# CameraCageBB.net
KiCad netlist of a schematic drawn in Altium Designer
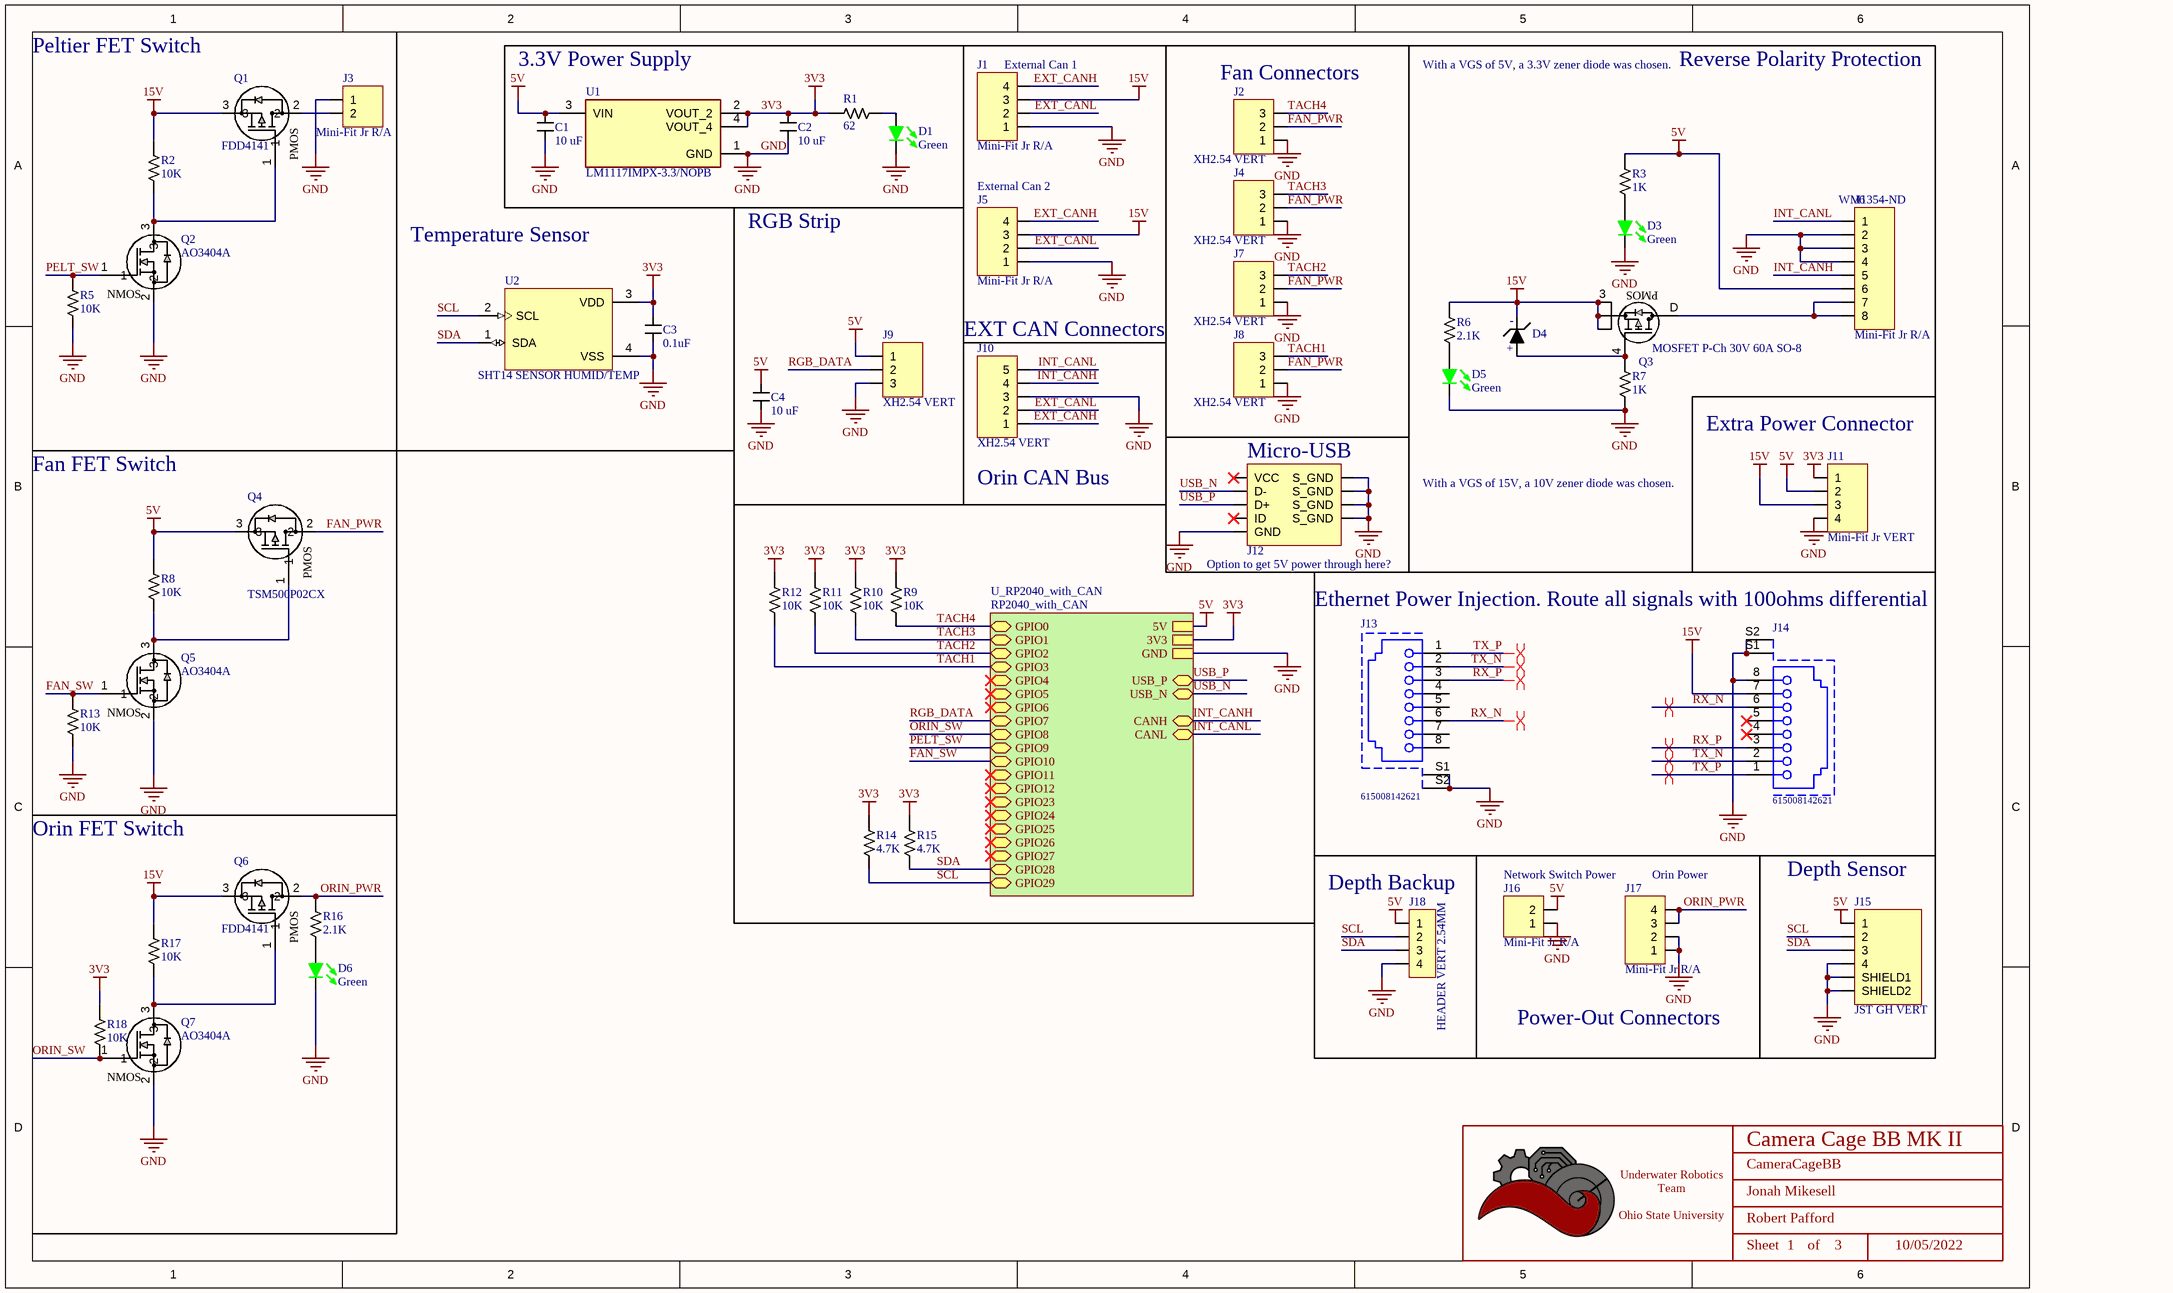
[diagram p0: CameraCageBB.SchDoc]

(export (version "E")
  (design (tool "Eeschema 10.0.6"))
  (components
    (comp (ref "*")
      (value "Title_Block")
      (footprint "LOGO")
      (description "UWRT Schematic Title Block Template\r\n\r\nCreated June 2021, Dylan Trainor")
      (libsource (lib "UWRT") (part "Title_Block"))
    )
    (comp (ref "C1")
      (value "10uF Ceramic 6.3V")
      (footprint "CAPACITOR_0603")
      (description "Cap 10uF 6.3V +/-20%\r\nCeramic 0603")
      (fields
        (field (name "TOLERANCE") "+/- 20%")
        (field (name "VOLTAGE") "6.3V")
        (field (name "VALUE (UF)") "10 uF")
        (field (name "MADE BY") "Flip B")
      )
      (libsource (lib "Capacitors") (part "CAPACITOR_10uF_0603"))
    )
    (comp (ref "C2")
      (value "10uF Ceramic 6.3V")
      (footprint "CAPACITOR_0603")
      (description "Cap 10uF 6.3V +/-20%\r\nCeramic 0603")
      (fields
        (field (name "TOLERANCE") "+/- 20%")
        (field (name "VOLTAGE") "6.3V")
        (field (name "VALUE (UF)") "10 uF")
        (field (name "MADE BY") "Flip B")
      )
      (libsource (lib "Capacitors") (part "CAPACITOR_10uF_0603"))
    )
    (comp (ref "C3")
      (value "0.1uF")
      (footprint "CAPACITOR_0603")
      (description "Cap 100nF 6.3V +/-10%\r\nCeramic 0603")
      (fields
        (field (name "TOLERANCE") "+/- 10%")
        (field (name "VOLTAGE") "6.3V")
        (field (name "MADE BY") "Flip B")
      )
      (libsource (lib "Capacitors") (part "CAPACITOR_0.1uF_0603"))
    )
    (comp (ref "C4")
      (value "10uF Ceramic 6.3V")
      (footprint "CAPACITOR_0603")
      (description "Cap 10uF 6.3V +/-20%\r\nCeramic 0603")
      (fields
        (field (name "TOLERANCE") "+/- 20%")
        (field (name "VOLTAGE") "6.3V")
        (field (name "VALUE (UF)") "10 uF")
        (field (name "MADE BY") "Flip B")
      )
      (libsource (lib "Capacitors") (part "CAPACITOR_10uF_0603"))
    )
    (comp (ref "D1")
      (value "IN-S63AT5G")
      (footprint "LED_0603")
      (description "LED Green Vf= 3V If = 0.005A\r\nIN-S63AT5G")
      (fields (field (name "COLOR") "Green") (field (name "MADE BY") "Robert Pafford"))
      (libsource (lib "Diodes") (part "LED_Green_0603_3V"))
    )
    (comp (ref "D3")
      (value "IN-S63AT5G")
      (footprint "LED_0603")
      (description "LED Green Vf= 3V If = 0.005A\r\nIN-S63AT5G")
      (fields (field (name "COLOR") "Green") (field (name "MADE BY") "Robert Pafford"))
      (libsource (lib "Diodes") (part "LED_Green_0603_3V"))
    )
    (comp (ref "D4")
      (value "Zener_Diode_10V_410mW")
      (footprint "SOD-123")
      (description "Zener Diode ¦ 10 V ¦ 410 mW ¦ SOD 123")
      (fields (field (name "POWER") "410mW") (field (name "MADE BY") "Nathan A"))
      (libsource (lib "Diodes") (part "Zener_Diode_10V_410mW"))
    )
    (comp (ref "D5")
      (value "IN-S63AT5G")
      (footprint "LED_0603")
      (description "LED Green Vf= 3V If = 0.005A\r\nIN-S63AT5G")
      (fields (field (name "COLOR") "Green") (field (name "MADE BY") "Robert Pafford"))
      (libsource (lib "Diodes") (part "LED_Green_0603_3V"))
    )
    (comp (ref "D6")
      (value "IN-S63AT5G")
      (footprint "LED_0603")
      (description "LED Green Vf= 3V If = 0.005A\r\nIN-S63AT5G")
      (fields (field (name "COLOR") "Green") (field (name "MADE BY") "Robert Pafford"))
      (libsource (lib "Diodes") (part "LED_Green_0603_3V"))
    )
    (comp (ref "J1")
      (value "Mini-Fit Jr R/A")
      (footprint "CONN_MOLEX_MINIFIT JR_4 POS_R/A")
      (description "Molex Minifit Jr. 5569 \r\n4 Pos R/A Natural")
      (fields (field (name "MANUFACTURER") "Molex") (field (name "CREATED BY") "Flip B"))
      (libsource (lib "Connectors") (part "CONN_MOLEX_MINIFIT JR_4POS_R/A"))
    )
    (comp (ref "J2")
      (value "XH2.54 VERT")
      (footprint "CONN_JST_XH254_3POS_VERT")
      (description "JST XH 2.54mm Pitch 3 Pos Vertical")
      (fields (field (name "MANUFACTURER") "JST") (field (name "CREATED BY") "Robert P"))
      (libsource (lib "") (part "CONN_JST_XH254_3POS_VERT_1"))
    )
    (comp (ref "J3")
      (value "Mini-Fit Jr R/A")
      (footprint "CONN_MOLEX_MINIFIT JR_2 POS_R/A")
      (description "Molex Minifit Jr. 5569 \r\n2 Pos R/A Natural")
      (fields (field (name "MANUFACTURER") "Molex") (field (name "CREATED BY") "Robert P"))
      (libsource (lib "Connectors") (part "CONN_MOLEX_MINIFIT JR_2POS_R/A"))
    )
    (comp (ref "J4")
      (value "XH2.54 VERT")
      (footprint "CONN_JST_XH254_3POS_VERT")
      (description "JST XH 2.54mm Pitch 3 Pos Vertical")
      (fields (field (name "MANUFACTURER") "JST") (field (name "CREATED BY") "Robert P"))
      (libsource (lib "") (part "CONN_JST_XH254_3POS_VERT_1"))
    )
    (comp (ref "J5")
      (value "Mini-Fit Jr R/A")
      (footprint "CONN_MOLEX_MINIFIT JR_4 POS_R/A")
      (description "Molex Minifit Jr. 5569 \r\n4 Pos R/A Natural")
      (fields (field (name "MANUFACTURER") "Molex") (field (name "CREATED BY") "Flip B"))
      (libsource (lib "Connectors") (part "CONN_MOLEX_MINIFIT JR_4POS_R/A"))
    )
    (comp (ref "J6")
      (value "Mini-Fit Jr R/A")
      (footprint "CONN_MOLEX_MINIFIT JR_8 POS_R/A")
      (description "Molex Minifit Jr. 5569 \r\n8 Pos R/A Natural")
      (fields
        (field (name "MANUFACTURER") "Molex")
        (field (name "SUPPLIER PART NUMBER 1") "WM1354-ND")
        (field (name "CREATED BY") "Flip B")
      )
      (libsource (lib "Connectors") (part "CONN_MOLEX_MINIFIT JR_8POS_R/A"))
    )
    (comp (ref "J7")
      (value "XH2.54 VERT")
      (footprint "CONN_JST_XH254_3POS_VERT")
      (description "JST XH 2.54mm Pitch 3 Pos Vertical")
      (fields (field (name "MANUFACTURER") "JST") (field (name "CREATED BY") "Robert P"))
      (libsource (lib "") (part "CONN_JST_XH254_3POS_VERT_1"))
    )
    (comp (ref "J8")
      (value "XH2.54 VERT")
      (footprint "CONN_JST_XH254_3POS_VERT")
      (description "JST XH 2.54mm Pitch 3 Pos Vertical")
      (fields (field (name "MANUFACTURER") "JST") (field (name "CREATED BY") "Robert P"))
      (libsource (lib "") (part "CONN_JST_XH254_3POS_VERT_1"))
    )
    (comp (ref "J9")
      (value "XH2.54 VERT")
      (footprint "CONN_JST_XH254_3POS_VERT")
      (description "JST XH 2.54mm Pitch 3 Pos Vertical")
      (fields (field (name "MANUFACTURER") "JST") (field (name "CREATED BY") "Robert P"))
      (libsource (lib "Connectors") (part "CONN_JST_XH254_3POS_VERT"))
    )
    (comp (ref "J10")
      (value "XH2.54 VERT")
      (footprint "CONN_JST_XH254_5POS_VERT")
      (description "JST XH 2.54mm Pitch 5 Pos Vertical")
      (fields (field (name "MANUFACTURER") "JST") (field (name "CREATED BY") "Robert P"))
      (libsource (lib "Connectors") (part "CONN_JST_XH254_5POS_VERT"))
    )
    (comp (ref "J11")
      (value "Mini-Fit Jr VERT")
      (footprint "CONN_MOLEX_MINIFIT JR_4 POS_VERT")
      (description "Molex Minifit Jr. 5566 \r\n4 Pos Vertical Natural")
      (fields (field (name "MANUFACTURER") "Molex") (field (name "CREATED BY") "Robert P"))
      (libsource (lib "Connectors") (part "CONN_MOLEX_MINIFIT JR_4POS_VERT"))
    )
    (comp (ref "J12")
      (value "USB_MICRO R/A")
      (footprint "CONN_MINIUSB")
      (description "Amphenol Micro USB-B\r\nUSB2.0 5 Pin Right Angle SMD")
      (fields (field (name "MANUFACTURER") "Amphenol") (field (name "CREATED BY") "Flip B"))
      (libsource (lib "Connectors") (part "CONN_MICROUSB"))
    )
    (comp (ref "J13")
      (value "615008142621")
      (footprint "615008142621")
      (fields (field (name "MANUFACTURER") "Wurth Elektronik") (field (name "PUBLISHER") "WurthElektronik"))
      (libsource (lib "Altium Content Vault") (part "WE-CN-1P-2F-J8"))
    )
    (comp (ref "J14")
      (value "615008142621")
      (footprint "615008142621")
      (fields (field (name "MANUFACTURER") "Wurth Elektronik") (field (name "PUBLISHER") "WurthElektronik"))
      (libsource (lib "Altium Content Vault") (part "WE-CN-1P-2F-J8"))
    )
    (comp (ref "J15")
      (value "JST GH VERT")
      (footprint "CONN_JST_BM04B-GHS-TBT(LF)(SN)(N)")
      (description "JST GH Pitch 4 Pos Vertical")
      (fields (field (name "MANUFACTURER") "JST") (field (name "CREATED BY") "Robert P"))
      (libsource (lib "Connectors") (part "CONN_JST_GH_4POS_VERT"))
    )
    (comp (ref "J16")
      (value "Mini-Fit Jr R/A")
      (footprint "CONN_MOLEX_MINIFIT JR_2 POS_R/A")
      (description "Molex Minifit Jr. 5569 \r\n2 Pos R/A Natural")
      (fields (field (name "MANUFACTURER") "Molex") (field (name "CREATED BY") "Robert P"))
      (libsource (lib "") (part "CONN_MOLEX_MINIFIT JR_2POS_R/A_1"))
    )
    (comp (ref "J17")
      (value "Mini-Fit Jr R/A")
      (footprint "CONN_MOLEX_MINIFIT JR_4 POS_R/A")
      (description "Molex Minifit Jr. 5569 \r\n4 Pos R/A Natural")
      (fields (field (name "MANUFACTURER") "Molex") (field (name "CREATED BY") "Flip B"))
      (libsource (lib "Connectors") (part "CONN_MOLEX_MINIFIT JR_4POS_R/A"))
    )
    (comp (ref "J18")
      (value "HEADER VERT 2.54MM")
      (footprint "HEADER_4PIN_2.54MM")
      (description "CONN HEADER VERT 4POS 2.54MM")
      (fields (field (name "MADE BY") "Robert Pafford"))
      (libsource (lib "Connectors") (part "HEADER_4PIN_2.54MM"))
    )
    (comp (ref "Q1")
      (value "FDD4141")
      (footprint "DPAK_ONS")
      (description "P-Channel 10.8A (Ta), 50A (Tc) 2.4W (Ta), 69W (Tc) Surface Mount D-PAK (TO-252AA)")
      (fields (field (name "CREATED BY") "Dylan T"))
      (libsource (lib "Transistors") (part "FDD4141"))
    )
    (comp (ref "Q2")
      (value "AO3404A")
      (footprint "SOT-23-3")
      (description "N-Channel 30 V 5.8A (Ta) 1.4W (Ta) Surface Mount SOT-23-3")
      (fields (field (name "CREATED BY") "Dylan T"))
      (libsource (lib "Transistors") (part "AO3404A"))
    )
    (comp (ref "Q3")
      (value "MOSFET P-Ch 30V 60A SO-8")
      (footprint "MOSFET_7DP-T1-GE3_VIS")
      (description "P-Channel 30 V 60A (Tc) 65.8W (Tc) Surface Mount PowerPAK® SO-8")
      (fields
        (field (name "MANUFACTURER_PART_NUMBER") "SIR167DP-T1-GE3")
        (field (name "COPYRIGHT") "Copyright (C) 2022 Ultra Librarian. All rights reserved.")
      )
      (libsource (lib "Transistors") (part "SIR167DP-T1-GE3"))
    )
    (comp (ref "Q4")
      (value "TSM500P02CX")
      (footprint "SOT-23-3")
      (description "P-Channel 20 V 4.7A (Tc) 1.56W (Tc) Surface Mount SOT-23")
      (fields (field (name "CREATED BY") "Robert Pafford"))
      (libsource (lib "Transistors") (part "TSM500P02CX"))
    )
    (comp (ref "Q5")
      (value "AO3404A")
      (footprint "SOT-23-3")
      (description "N-Channel 30 V 5.8A (Ta) 1.4W (Ta) Surface Mount SOT-23-3")
      (fields (field (name "CREATED BY") "Dylan T"))
      (libsource (lib "Transistors") (part "AO3404A"))
    )
    (comp (ref "Q6")
      (value "FDD4141")
      (footprint "DPAK_ONS")
      (description "P-Channel 10.8A (Ta), 50A (Tc) 2.4W (Ta), 69W (Tc) Surface Mount D-PAK (TO-252AA)")
      (fields (field (name "CREATED BY") "Dylan T"))
      (libsource (lib "Transistors") (part "FDD4141"))
    )
    (comp (ref "Q7")
      (value "AO3404A")
      (footprint "SOT-23-3")
      (description "N-Channel 30 V 5.8A (Ta) 1.4W (Ta) Surface Mount SOT-23-3")
      (fields (field (name "CREATED BY") "Dylan T"))
      (libsource (lib "Transistors") (part "AO3404A"))
    )
    (comp (ref "R1")
      (value "62 Ohm 1% 1/4W")
      (footprint "RESISTOR_0603")
      (description "RES SMD 62 OHM 1% 1/4W 0603")
      (fields
        (field (name "TOLERANCE") "+/- 1%")
        (field (name "VALUE  (OHMS)") "62")
        (field (name "MADE BY") "Robert Pafford")
      )
      (libsource (lib "Resistors") (part "RESISTOR_62_0603"))
    )
    (comp (ref "R2")
      (value "10k Ohm 5% 1/10W")
      (footprint "RESISTOR_0603")
      (description "RES 10k OHM 5% 1/10W 0603")
      (fields
        (field (name "TOLERANCE") "+/- 5%")
        (field (name "VALUE  (OHMS)") "10K")
        (field (name "MADE BY") "Robert Pafford")
      )
      (libsource (lib "Resistors") (part "RESISTOR_10K_0603"))
    )
    (comp (ref "R3")
      (value "1k Ohm 5% 1/8W")
      (footprint "RESISTOR_0603")
      (description "RES 1k OHM 5% 1/8W 0603")
      (fields
        (field (name "TOLERANCE") "+/- 5%")
        (field (name "VALUE  (OHMS)") "1K")
        (field (name "MADE BY") "Robert Pafford")
      )
      (libsource (lib "Resistors") (part "RESISTOR_1K_0603"))
    )
    (comp (ref "R5")
      (value "10k Ohm 5% 1/10W")
      (footprint "RESISTOR_0603")
      (description "RES 10k OHM 5% 1/10W 0603")
      (fields
        (field (name "TOLERANCE") "+/- 5%")
        (field (name "VALUE  (OHMS)") "10K")
        (field (name "MADE BY") "Robert Pafford")
      )
      (libsource (lib "Resistors") (part "RESISTOR_10K_0603"))
    )
    (comp (ref "R6")
      (value "2.1k Ohm 5% 1/8W")
      (footprint "RESISTOR_0603")
      (description "RES 2.1k OHM 5% 1/8W 0603")
      (fields
        (field (name "TOLERANCE") "+/- 5%")
        (field (name "VALUE  (OHMS)") "2.1K")
        (field (name "MADE BY") "Robert Pafford")
      )
      (libsource (lib "Resistors") (part "RESISTOR_2.1K_0603"))
    )
    (comp (ref "R7")
      (value "1k Ohm 5% 1/8W")
      (footprint "RESISTOR_0603")
      (description "RES 1k OHM 5% 1/8W 0603")
      (fields
        (field (name "TOLERANCE") "+/- 5%")
        (field (name "VALUE  (OHMS)") "1K")
        (field (name "MADE BY") "Robert Pafford")
      )
      (libsource (lib "Resistors") (part "RESISTOR_1K_0603"))
    )
    (comp (ref "R8")
      (value "10k Ohm 5% 1/10W")
      (footprint "RESISTOR_0603")
      (description "RES 10k OHM 5% 1/10W 0603")
      (fields
        (field (name "TOLERANCE") "+/- 5%")
        (field (name "VALUE  (OHMS)") "10K")
        (field (name "MADE BY") "Robert Pafford")
      )
      (libsource (lib "Resistors") (part "RESISTOR_10K_0603"))
    )
    (comp (ref "R9")
      (value "10k Ohm 5% 1/10W")
      (footprint "RESISTOR_0603")
      (description "RES 10k OHM 5% 1/10W 0603")
      (fields
        (field (name "TOLERANCE") "+/- 5%")
        (field (name "VALUE  (OHMS)") "10K")
        (field (name "MADE BY") "Robert Pafford")
      )
      (libsource (lib "Resistors") (part "RESISTOR_10K_0603"))
    )
    (comp (ref "R10")
      (value "10k Ohm 5% 1/10W")
      (footprint "RESISTOR_0603")
      (description "RES 10k OHM 5% 1/10W 0603")
      (fields
        (field (name "TOLERANCE") "+/- 5%")
        (field (name "VALUE  (OHMS)") "10K")
        (field (name "MADE BY") "Robert Pafford")
      )
      (libsource (lib "Resistors") (part "RESISTOR_10K_0603"))
    )
    (comp (ref "R11")
      (value "10k Ohm 5% 1/10W")
      (footprint "RESISTOR_0603")
      (description "RES 10k OHM 5% 1/10W 0603")
      (fields
        (field (name "TOLERANCE") "+/- 5%")
        (field (name "VALUE  (OHMS)") "10K")
        (field (name "MADE BY") "Robert Pafford")
      )
      (libsource (lib "Resistors") (part "RESISTOR_10K_0603"))
    )
    (comp (ref "R12")
      (value "10k Ohm 5% 1/10W")
      (footprint "RESISTOR_0603")
      (description "RES 10k OHM 5% 1/10W 0603")
      (fields
        (field (name "TOLERANCE") "+/- 5%")
        (field (name "VALUE  (OHMS)") "10K")
        (field (name "MADE BY") "Robert Pafford")
      )
      (libsource (lib "Resistors") (part "RESISTOR_10K_0603"))
    )
    (comp (ref "R13")
      (value "10k Ohm 5% 1/10W")
      (footprint "RESISTOR_0603")
      (description "RES 10k OHM 5% 1/10W 0603")
      (fields
        (field (name "TOLERANCE") "+/- 5%")
        (field (name "VALUE  (OHMS)") "10K")
        (field (name "MADE BY") "Robert Pafford")
      )
      (libsource (lib "Resistors") (part "RESISTOR_10K_0603"))
    )
    (comp (ref "R14")
      (value "4.7k Ohm 5% 1/10W")
      (footprint "RESISTOR_0603")
      (description "RES 4.7k OHM 5% 1/10W 0603")
      (fields
        (field (name "TOLERANCE") "+/- 5%")
        (field (name "VALUE  (OHMS)") "4.7K")
        (field (name "MADE BY") "Robert Pafford")
      )
      (libsource (lib "Resistors") (part "RESISTOR_4.7K_0603"))
    )
    (comp (ref "R15")
      (value "4.7k Ohm 5% 1/10W")
      (footprint "RESISTOR_0603")
      (description "RES 4.7k OHM 5% 1/10W 0603")
      (fields
        (field (name "TOLERANCE") "+/- 5%")
        (field (name "VALUE  (OHMS)") "4.7K")
        (field (name "MADE BY") "Robert Pafford")
      )
      (libsource (lib "Resistors") (part "RESISTOR_4.7K_0603"))
    )
    (comp (ref "R16")
      (value "2.1k Ohm 5% 1/8W")
      (footprint "RESISTOR_0603")
      (description "RES 2.1k OHM 5% 1/8W 0603")
      (fields
        (field (name "TOLERANCE") "+/- 5%")
        (field (name "VALUE  (OHMS)") "2.1K")
        (field (name "MADE BY") "Robert Pafford")
      )
      (libsource (lib "Resistors") (part "RESISTOR_2.1K_0603"))
    )
    (comp (ref "R17")
      (value "10k Ohm 5% 1/10W")
      (footprint "RESISTOR_0603")
      (description "RES 10k OHM 5% 1/10W 0603")
      (fields
        (field (name "TOLERANCE") "+/- 5%")
        (field (name "VALUE  (OHMS)") "10K")
        (field (name "MADE BY") "Robert Pafford")
      )
      (libsource (lib "Resistors") (part "RESISTOR_10K_0603"))
    )
    (comp (ref "R18")
      (value "10k Ohm 5% 1/10W")
      (footprint "RESISTOR_0603")
      (description "RES 10k OHM 5% 1/10W 0603")
      (fields
        (field (name "TOLERANCE") "+/- 5%")
        (field (name "VALUE  (OHMS)") "10K")
        (field (name "MADE BY") "Robert Pafford")
      )
      (libsource (lib "Resistors") (part "RESISTOR_10K_0603"))
    )
    (comp (ref "U1")
      (value "LM1117IMPX-3.3/NOPB")
      (footprint "SOT-223-4")
      (description "800-mA 15-V linear voltage regulator 4-SOT-223 -40 to 125")
      (fields (field (name "MF") "Texas Instruments"))
      (libsource (lib "Integrated Circuits") (part "LM1117IMPX-3.3/NOPB"))
    )
    (comp (ref "U2")
      (value "SHT14 SENSOR HUMID/TEMP")
      (footprint "XDCR_SHT41-AD1B-R2")
      (description "Digital Relative Humidity Temperature Sensor, Â±1.8 / max 2.5 %RH, Â±0.2 Â°C, Ultra-Low-Power")
      (fields (field (name "MP") "SHT41-AD1B-R2") (field (name "MF") "Sensirion"))
      (libsource (lib "Integrated Circuits") (part "SHT41-AD1B-R2"))
    )
  )
  (nets
    (net (code "1") (name "/EXT_CANH") (class "Default")
      (node (ref "J1") (pin "4") (pinfunction "4_4") (pintype "passive"))
      (node (ref "J10") (pin "1") (pinfunction "1_1") (pintype "passive"))
      (node (ref "J5") (pin "4") (pinfunction "4_4") (pintype "passive"))
    )
    (net (code "2") (name "/EXT_CANL") (class "Default")
      (node (ref "J1") (pin "2") (pinfunction "2_2") (pintype "passive"))
      (node (ref "J10") (pin "2") (pinfunction "2_2") (pintype "passive"))
      (node (ref "J5") (pin "2") (pinfunction "2_2") (pintype "passive"))
    )
    (net (code "3") (name "/FAN_PWR") (class "Default")
      (node (ref "J2") (pin "2") (pinfunction "2_2") (pintype "passive"))
      (node (ref "J4") (pin "2") (pinfunction "2_2") (pintype "passive"))
      (node (ref "J7") (pin "2") (pinfunction "2_2") (pintype "passive"))
      (node (ref "J8") (pin "2") (pinfunction "2_2") (pintype "passive"))
      (node (ref "Q4") (pin "2") (pinfunction "2_2") (pintype "passive"))
    )
    (net (code "4") (name "/FAN_SW") (class "Default")
      (node (ref "Q5") (pin "1") (pinfunction "1_1") (pintype "passive"))
      (node (ref "R13") (pin "1") (pinfunction "1_1") (pintype "passive"))
    )
    (net (code "15") (name "/INT_CANH") (class "Default")
      (node (ref "J10") (pin "4") (pinfunction "4_4") (pintype "passive"))
      (node (ref "J6") (pin "5") (pinfunction "5_5") (pintype "passive"))
    )
    (net (code "16") (name "/INT_CANL") (class "Default")
      (node (ref "J10") (pin "5") (pinfunction "5_5") (pintype "passive"))
      (node (ref "J6") (pin "1") (pinfunction "1_1") (pintype "passive"))
    )
    (net (code "17") (name "/ORIN_PWR") (class "Default")
      (node (ref "J17") (pin "3") (pinfunction "3_3") (pintype "passive"))
      (node (ref "J17") (pin "4") (pinfunction "4_4") (pintype "passive"))
      (node (ref "Q6") (pin "2") (pinfunction "2_2") (pintype "passive"))
      (node (ref "R16") (pin "1") (pinfunction "1_1") (pintype "passive"))
    )
    (net (code "18") (name "/ORIN_SW") (class "Default")
      (node (ref "Q7") (pin "1") (pinfunction "1_1") (pintype "passive"))
      (node (ref "R18") (pin "2") (pinfunction "2_2") (pintype "passive"))
    )
    (net (code "19") (name "/PELT_SW") (class "Default")
      (node (ref "Q2") (pin "1") (pinfunction "1_1") (pintype "passive"))
      (node (ref "R5") (pin "1") (pinfunction "1_1") (pintype "passive"))
    )
    (net (code "20") (name "/RGB_DATA") (class "Default")
      (node (ref "J9") (pin "2") (pinfunction "2_2") (pintype "passive"))
    )
    (net (code "21") (name "/RX_N") (class "Default")
      (node (ref "J13") (pin "6") (pinfunction "6_6") (pintype "passive"))
      (node (ref "J14") (pin "6") (pinfunction "6_6") (pintype "passive"))
    )
    (net (code "22") (name "/RX_P") (class "Default")
      (node (ref "J13") (pin "3") (pinfunction "3_3") (pintype "passive"))
      (node (ref "J14") (pin "3") (pinfunction "3_3") (pintype "passive"))
    )
    (net (code "23") (name "/SCL") (class "Default")
      (node (ref "J15") (pin "2") (pinfunction "2_2") (pintype "passive"))
      (node (ref "J18") (pin "2") (pinfunction "2_2") (pintype "passive"))
      (node (ref "R14") (pin "2") (pinfunction "2_2") (pintype "passive"))
      (node (ref "U2") (pin "2") (pinfunction "SCL_2") (pintype "input"))
    )
    (net (code "24") (name "/SDA") (class "Default")
      (node (ref "J15") (pin "3") (pinfunction "3_3") (pintype "passive"))
      (node (ref "J18") (pin "3") (pinfunction "3_3") (pintype "passive"))
      (node (ref "R15") (pin "2") (pinfunction "2_2") (pintype "passive"))
      (node (ref "U2") (pin "1") (pinfunction "SDA_1") (pintype "bidirectional"))
    )
    (net (code "25") (name "/TACH1") (class "Default")
      (node (ref "J8") (pin "3") (pinfunction "3_3") (pintype "passive"))
      (node (ref "R12") (pin "2") (pinfunction "2_2") (pintype "passive"))
    )
    (net (code "26") (name "/TACH2") (class "Default")
      (node (ref "J7") (pin "3") (pinfunction "3_3") (pintype "passive"))
      (node (ref "R11") (pin "2") (pinfunction "2_2") (pintype "passive"))
    )
    (net (code "27") (name "/TACH3") (class "Default")
      (node (ref "J4") (pin "3") (pinfunction "3_3") (pintype "passive"))
      (node (ref "R10") (pin "2") (pinfunction "2_2") (pintype "passive"))
    )
    (net (code "28") (name "/TACH4") (class "Default")
      (node (ref "J2") (pin "3") (pinfunction "3_3") (pintype "passive"))
      (node (ref "R9") (pin "2") (pinfunction "2_2") (pintype "passive"))
    )
    (net (code "29") (name "/TX_N") (class "Default")
      (node (ref "J13") (pin "2") (pinfunction "2_2") (pintype "passive"))
      (node (ref "J14") (pin "2") (pinfunction "2_2") (pintype "passive"))
    )
    (net (code "30") (name "/TX_P") (class "Default")
      (node (ref "J13") (pin "1") (pinfunction "1_1") (pintype "passive"))
      (node (ref "J14") (pin "1") (pinfunction "1_1") (pintype "passive"))
    )
    (net (code "31") (name "/USB_N") (class "Default")
      (node (ref "J12") (pin "2") (pinfunction "D-_2") (pintype "passive"))
    )
    (net (code "32") (name "/USB_P") (class "Default")
      (node (ref "J12") (pin "3") (pinfunction "D+_3") (pintype "passive"))
    )
    (net (code "33") (name "3V3") (class "Default")
      (node (ref "C2") (pin "1") (pinfunction "1_1") (pintype "passive"))
      (node (ref "C3") (pin "1") (pinfunction "1_1") (pintype "passive"))
      (node (ref "J11") (pin "1") (pinfunction "1_1") (pintype "passive"))
      (node (ref "R1") (pin "1") (pinfunction "1_1") (pintype "passive"))
      (node (ref "R10") (pin "1") (pinfunction "1_1") (pintype "passive"))
      (node (ref "R11") (pin "1") (pinfunction "1_1") (pintype "passive"))
      (node (ref "R12") (pin "1") (pinfunction "1_1") (pintype "passive"))
      (node (ref "R14") (pin "1") (pinfunction "1_1") (pintype "passive"))
      (node (ref "R15") (pin "1") (pinfunction "1_1") (pintype "passive"))
      (node (ref "R18") (pin "1") (pinfunction "1_1") (pintype "passive"))
      (node (ref "R9") (pin "1") (pinfunction "1_1") (pintype "passive"))
      (node (ref "U1") (pin "2") (pinfunction "VOUT_2_2") (pintype "power_in"))
      (node (ref "U1") (pin "4") (pinfunction "VOUT_4_4") (pintype "power_in"))
      (node (ref "U2") (pin "3") (pinfunction "VDD_3") (pintype "power_in"))
    )
    (net (code "34") (name "5V") (class "Default")
      (node (ref "C1") (pin "1") (pinfunction "1_1") (pintype "passive"))
      (node (ref "C4") (pin "1") (pinfunction "1_1") (pintype "passive"))
      (node (ref "J11") (pin "2") (pinfunction "2_2") (pintype "passive"))
      (node (ref "J15") (pin "1") (pinfunction "1_1") (pintype "passive"))
      (node (ref "J16") (pin "2") (pinfunction "2_2") (pintype "passive"))
      (node (ref "J18") (pin "1") (pinfunction "1_1") (pintype "passive"))
      (node (ref "J6") (pin "6") (pinfunction "6_6") (pintype "passive"))
      (node (ref "J9") (pin "1") (pinfunction "1_1") (pintype "passive"))
      (node (ref "Q4") (pin "3") (pinfunction "3_3") (pintype "passive"))
      (node (ref "R3") (pin "1") (pinfunction "1_1") (pintype "passive"))
      (node (ref "R8") (pin "1") (pinfunction "1_1") (pintype "passive"))
      (node (ref "U1") (pin "3") (pinfunction "VIN_3") (pintype "power_in"))
    )
    (net (code "35") (name "15V") (class "Default")
      (node (ref "D4") (pin "2") (pinfunction "2_2") (pintype "passive"))
      (node (ref "J1") (pin "3") (pinfunction "3_3") (pintype "passive"))
      (node (ref "J11") (pin "3") (pinfunction "3_3") (pintype "passive"))
      (node (ref "J14") (pin "7") (pinfunction "7_7") (pintype "passive"))
      (node (ref "J5") (pin "3") (pinfunction "3_3") (pintype "passive"))
      (node (ref "Q1") (pin "3") (pinfunction "3_3") (pintype "passive"))
      (node (ref "Q3") (pin "1") (pinfunction "S_1") (pintype "passive"))
      (node (ref "Q3") (pin "2") (pinfunction "S_2") (pintype "passive"))
      (node (ref "Q3") (pin "3") (pinfunction "S_3") (pintype "passive"))
      (node (ref "Q6") (pin "3") (pinfunction "3_3") (pintype "passive"))
      (node (ref "R17") (pin "1") (pinfunction "1_1") (pintype "passive"))
      (node (ref "R2") (pin "1") (pinfunction "1_1") (pintype "passive"))
      (node (ref "R6") (pin "1") (pinfunction "1_1") (pintype "passive"))
    )
    (net (code "36") (name "GND") (class "Default")
      (node (ref "C1") (pin "2") (pinfunction "2_2") (pintype "passive"))
      (node (ref "C2") (pin "2") (pinfunction "2_2") (pintype "passive"))
      (node (ref "C3") (pin "2") (pinfunction "2_2") (pintype "passive"))
      (node (ref "C4") (pin "2") (pinfunction "2_2") (pintype "passive"))
      (node (ref "D1") (pin "2") (pinfunction "2_2") (pintype "passive"))
      (node (ref "D3") (pin "2") (pinfunction "2_2") (pintype "passive"))
      (node (ref "D5") (pin "2") (pinfunction "2_2") (pintype "passive"))
      (node (ref "D6") (pin "2") (pinfunction "2_2") (pintype "passive"))
      (node (ref "J1") (pin "1") (pinfunction "1_1") (pintype "passive"))
      (node (ref "J10") (pin "3") (pinfunction "3_3") (pintype "passive"))
      (node (ref "J11") (pin "4") (pinfunction "4_4") (pintype "passive"))
      (node (ref "J12") (pin "5") (pinfunction "GND_5") (pintype "passive"))
      (node (ref "J12") (pin "6") (pinfunction "S_GND_6") (pintype "passive"))
      (node (ref "J12") (pin "7") (pinfunction "S_GND_7") (pintype "passive"))
      (node (ref "J12") (pin "8") (pinfunction "S_GND_8") (pintype "passive"))
      (node (ref "J12") (pin "9") (pinfunction "S_GND_9") (pintype "passive"))
      (node (ref "J13") (pin "S1") (pinfunction "S1_S1") (pintype "passive"))
      (node (ref "J13") (pin "S2") (pinfunction "S2_S2") (pintype "passive"))
      (node (ref "J14") (pin "8") (pinfunction "8_8") (pintype "passive"))
      (node (ref "J14") (pin "S1") (pinfunction "S1_S1") (pintype "passive"))
      (node (ref "J14") (pin "S2") (pinfunction "S2_S2") (pintype "passive"))
      (node (ref "J15") (pin "4") (pinfunction "4_4") (pintype "passive"))
      (node (ref "J15") (pin "S1") (pinfunction "SHIELD1_S1") (pintype "passive"))
      (node (ref "J15") (pin "S2") (pinfunction "SHIELD2_S2") (pintype "passive"))
      (node (ref "J16") (pin "1") (pinfunction "1_1") (pintype "passive"))
      (node (ref "J17") (pin "1") (pinfunction "1_1") (pintype "passive"))
      (node (ref "J17") (pin "2") (pinfunction "2_2") (pintype "passive"))
      (node (ref "J18") (pin "4") (pinfunction "4_4") (pintype "passive"))
      (node (ref "J2") (pin "1") (pinfunction "1_1") (pintype "passive"))
      (node (ref "J3") (pin "1") (pinfunction "1_1") (pintype "passive"))
      (node (ref "J4") (pin "1") (pinfunction "1_1") (pintype "passive"))
      (node (ref "J5") (pin "1") (pinfunction "1_1") (pintype "passive"))
      (node (ref "J6") (pin "2") (pinfunction "2_2") (pintype "passive"))
      (node (ref "J6") (pin "3") (pinfunction "3_3") (pintype "passive"))
      (node (ref "J6") (pin "4") (pinfunction "4_4") (pintype "passive"))
      (node (ref "J7") (pin "1") (pinfunction "1_1") (pintype "passive"))
      (node (ref "J8") (pin "1") (pinfunction "1_1") (pintype "passive"))
      (node (ref "J9") (pin "3") (pinfunction "3_3") (pintype "passive"))
      (node (ref "Q2") (pin "2") (pinfunction "2_2") (pintype "passive"))
      (node (ref "Q5") (pin "2") (pinfunction "2_2") (pintype "passive"))
      (node (ref "Q7") (pin "2") (pinfunction "2_2") (pintype "passive"))
      (node (ref "R13") (pin "2") (pinfunction "2_2") (pintype "passive"))
      (node (ref "R5") (pin "2") (pinfunction "2_2") (pintype "passive"))
      (node (ref "R7") (pin "2") (pinfunction "2_2") (pintype "passive"))
      (node (ref "U1") (pin "1") (pinfunction "GND_1") (pintype "power_in"))
      (node (ref "U2") (pin "4") (pinfunction "VSS_4") (pintype "power_in"))
    )
    (net (code "37") (name "Net-(D1-Pad1)") (class "Default")
      (node (ref "D1") (pin "1") (pinfunction "1_1") (pintype "passive"))
      (node (ref "R1") (pin "2") (pinfunction "2_2") (pintype "passive"))
    )
    (net (code "38") (name "Net-(D3-Pad1)") (class "Default")
      (node (ref "D3") (pin "1") (pinfunction "1_1") (pintype "passive"))
      (node (ref "R3") (pin "2") (pinfunction "2_2") (pintype "passive"))
    )
    (net (code "39") (name "Net-(D5-Pad1)") (class "Default")
      (node (ref "D5") (pin "1") (pinfunction "1_1") (pintype "passive"))
      (node (ref "R6") (pin "2") (pinfunction "2_2") (pintype "passive"))
    )
    (net (code "40") (name "Net-(D6-Pad1)") (class "Default")
      (node (ref "D6") (pin "1") (pinfunction "1_1") (pintype "passive"))
      (node (ref "R16") (pin "2") (pinfunction "2_2") (pintype "passive"))
    )
    (net (code "41") (name "Net-(J3-Pad2)") (class "Default")
      (node (ref "J3") (pin "2") (pinfunction "2_2") (pintype "passive"))
      (node (ref "Q1") (pin "2") (pinfunction "2_2") (pintype "passive"))
    )
    (net (code "42") (name "Net-(J6-Pad7)") (class "Default")
      (node (ref "J6") (pin "7") (pinfunction "7_7") (pintype "passive"))
      (node (ref "J6") (pin "8") (pinfunction "8_8") (pintype "passive"))
      (node (ref "Q3") (pin "D") (pinfunction "D_D") (pintype "passive"))
    )
    (net (code "43") (name "Net-(Q1-Pad1)") (class "Default")
      (node (ref "Q1") (pin "1") (pinfunction "1_1") (pintype "passive"))
      (node (ref "Q2") (pin "3") (pinfunction "3_3") (pintype "passive"))
      (node (ref "R2") (pin "2") (pinfunction "2_2") (pintype "passive"))
    )
    (net (code "44") (name "Net-(Q3-G)") (class "Default")
      (node (ref "D4") (pin "1") (pinfunction "1_1") (pintype "passive"))
      (node (ref "Q3") (pin "4") (pinfunction "G_4") (pintype "passive"))
      (node (ref "R7") (pin "1") (pinfunction "1_1") (pintype "passive"))
    )
    (net (code "45") (name "Net-(Q4-Pad1)") (class "Default")
      (node (ref "Q4") (pin "1") (pinfunction "1_1") (pintype "passive"))
      (node (ref "Q5") (pin "3") (pinfunction "3_3") (pintype "passive"))
      (node (ref "R8") (pin "2") (pinfunction "2_2") (pintype "passive"))
    )
    (net (code "46") (name "Net-(Q6-Pad1)") (class "Default")
      (node (ref "Q6") (pin "1") (pinfunction "1_1") (pintype "passive"))
      (node (ref "Q7") (pin "3") (pinfunction "3_3") (pintype "passive"))
      (node (ref "R17") (pin "2") (pinfunction "2_2") (pintype "passive"))
    )
    (net (code "47") (name "unconnected-(J12-ID-Pad4)") (class "Default")
      (node (ref "J12") (pin "4") (pinfunction "ID_4") (pintype "passive+no_connect"))
    )
    (net (code "48") (name "unconnected-(J12-VCC-Pad1)") (class "Default")
      (node (ref "J12") (pin "1") (pinfunction "VCC_1") (pintype "passive+no_connect"))
    )
    (net (code "49") (name "unconnected-(J13-Pad4)") (class "Default")
      (node (ref "J13") (pin "4") (pinfunction "4_4") (pintype "passive"))
    )
    (net (code "50") (name "unconnected-(J13-Pad5)") (class "Default")
      (node (ref "J13") (pin "5") (pinfunction "5_5") (pintype "passive"))
    )
    (net (code "51") (name "unconnected-(J13-Pad7)") (class "Default")
      (node (ref "J13") (pin "7") (pinfunction "7_7") (pintype "passive"))
    )
    (net (code "52") (name "unconnected-(J13-Pad8)") (class "Default")
      (node (ref "J13") (pin "8") (pinfunction "8_8") (pintype "passive"))
    )
    (net (code "53") (name "unconnected-(J14-Pad4)") (class "Default")
      (node (ref "J14") (pin "4") (pinfunction "4_4") (pintype "passive+no_connect"))
    )
    (net (code "54") (name "unconnected-(J14-Pad5)") (class "Default")
      (node (ref "J14") (pin "5") (pinfunction "5_5") (pintype "passive+no_connect"))
    )
  )
)
